# GZ7_1_x-User_Interface.net
KiCad netlist of a schematic drawn in Altium Designer
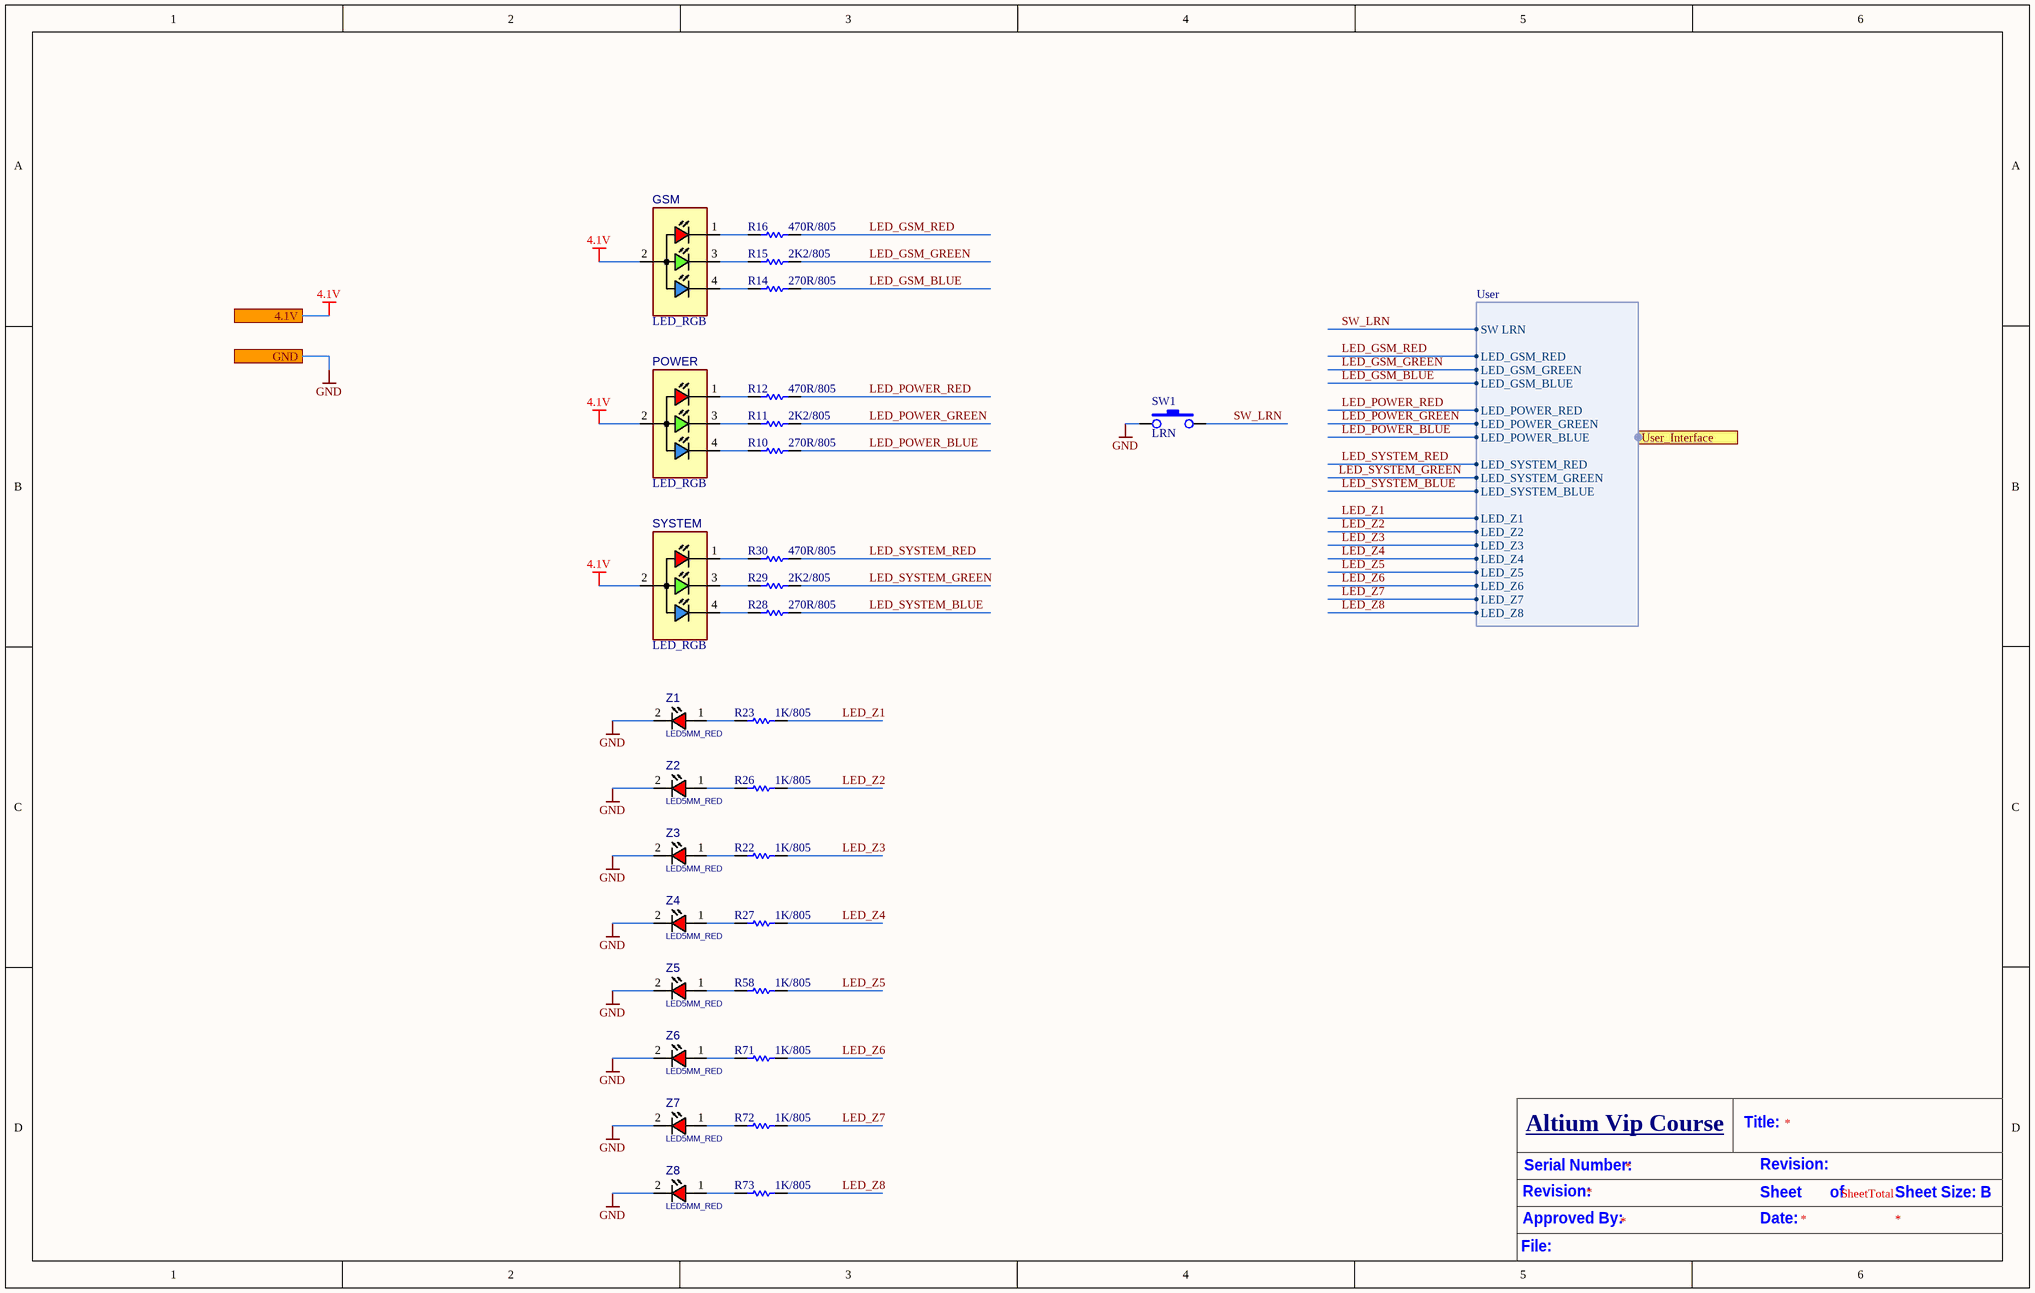
[diagram p0: GZ7_1_x-User_Interface.SchDoc]

(export (version "E")
  (design (tool "Eeschema 10.0.6"))
  (components
    (comp (ref "GSM")
      (value "LED_RGB")
      (footprint "LED5RGB")
      (description "LED, THD, 5MM, RGB COMMON CATHODE")
      (fields (field (name "MANF_P#") "YSL-R596CR3G4B5C-C10") (field (name "MANF") "CHINA YOUNG"))
      (libsource (lib "led(diode)") (part "LED_THD_5MM_RGB_CA"))
    )
    (comp (ref "POWER")
      (value "LED_RGB")
      (footprint "LED5RGB")
      (description "LED, THD, 5MM, RGB COMMON CATHODE")
      (fields (field (name "MANF_P#") "YSL-R596CR3G4B5C-C10") (field (name "MANF") "CHINA YOUNG"))
      (libsource (lib "led(diode)") (part "LED_THD_5MM_RGB_CA"))
    )
    (comp (ref "R10")
      (value "270R/805")
      (footprint "my805")
      (description "RES 805")
      (fields (field (name "DESIGNER") "Abbas Basereh"))
      (libsource (lib "Altium") (part "RES 1206 0.25W"))
    )
    (comp (ref "R11")
      (value "2K2/805")
      (footprint "my805")
      (description "RES 805")
      (fields (field (name "DESIGNER") "Abbas Basereh"))
      (libsource (lib "Altium") (part "RES 1206 0.25W"))
    )
    (comp (ref "R12")
      (value "470R/805")
      (footprint "my805")
      (description "RES 805")
      (fields (field (name "DESIGNER") "Abbas Basereh"))
      (libsource (lib "Altium") (part "RES 1206 0.25W"))
    )
    (comp (ref "R14")
      (value "270R/805")
      (footprint "my805")
      (description "RES 805")
      (fields (field (name "DESIGNER") "Abbas Basereh"))
      (libsource (lib "Altium") (part "RES 1206 0.25W"))
    )
    (comp (ref "R15")
      (value "2K2/805")
      (footprint "my805")
      (description "RES 805")
      (fields (field (name "DESIGNER") "Abbas Basereh"))
      (libsource (lib "Altium") (part "RES 1206 0.25W"))
    )
    (comp (ref "R16")
      (value "470R/805")
      (footprint "my805")
      (description "RES 805")
      (fields (field (name "DESIGNER") "Abbas Basereh"))
      (libsource (lib "Altium") (part "RES 1206 0.25W"))
    )
    (comp (ref "R22")
      (value "1K/805")
      (footprint "my805")
      (description "RES 805")
      (fields (field (name "DESIGNER") "Abbas Basereh"))
      (libsource (lib "Altium") (part "RES 1206 0.25W"))
    )
    (comp (ref "R23")
      (value "1K/805")
      (footprint "my805")
      (description "RES 805")
      (fields (field (name "DESIGNER") "Abbas Basereh"))
      (libsource (lib "Altium") (part "RES 1206 0.25W"))
    )
    (comp (ref "R26")
      (value "1K/805")
      (footprint "my805")
      (description "RES 805")
      (fields (field (name "DESIGNER") "Abbas Basereh"))
      (libsource (lib "Altium") (part "RES 1206 0.25W"))
    )
    (comp (ref "R27")
      (value "1K/805")
      (footprint "my805")
      (description "RES 805")
      (fields (field (name "DESIGNER") "Abbas Basereh"))
      (libsource (lib "Altium") (part "RES 1206 0.25W"))
    )
    (comp (ref "R28")
      (value "270R/805")
      (footprint "my805")
      (description "RES 805")
      (fields (field (name "DESIGNER") "Abbas Basereh"))
      (libsource (lib "Altium") (part "RES 1206 0.25W"))
    )
    (comp (ref "R29")
      (value "2K2/805")
      (footprint "my805")
      (description "RES 805")
      (fields (field (name "DESIGNER") "Abbas Basereh"))
      (libsource (lib "Altium") (part "RES 1206 0.25W"))
    )
    (comp (ref "R30")
      (value "470R/805")
      (footprint "my805")
      (description "RES 805")
      (fields (field (name "DESIGNER") "Abbas Basereh"))
      (libsource (lib "Altium") (part "RES 1206 0.25W"))
    )
    (comp (ref "R58")
      (value "1K/805")
      (footprint "my805")
      (description "RES 805")
      (fields (field (name "DESIGNER") "Abbas Basereh"))
      (libsource (lib "Altium") (part "RES 1206 0.25W"))
    )
    (comp (ref "R71")
      (value "1K/805")
      (footprint "my805")
      (description "RES 805")
      (fields (field (name "DESIGNER") "Abbas Basereh"))
      (libsource (lib "Altium") (part "RES 1206 0.25W"))
    )
    (comp (ref "R72")
      (value "1K/805")
      (footprint "my805")
      (description "RES 805")
      (fields (field (name "DESIGNER") "Abbas Basereh"))
      (libsource (lib "Altium") (part "RES 1206 0.25W"))
    )
    (comp (ref "R73")
      (value "1K/805")
      (footprint "my805")
      (description "RES 805")
      (fields (field (name "DESIGNER") "Abbas Basereh"))
      (libsource (lib "Altium") (part "RES 1206 0.25W"))
    )
    (comp (ref "SW1")
      (value "LRN")
      (footprint "SWPBS_SPST_6X3X5")
      (libsource (lib "AliPadash") (part "SW-PB"))
    )
    (comp (ref "SYSTEM")
      (value "LED_RGB")
      (footprint "LED5RGB")
      (description "LED, THD, 5MM, RGB COMMON CATHODE")
      (fields (field (name "MANF_P#") "YSL-R596CR3G4B5C-C10") (field (name "MANF") "CHINA YOUNG"))
      (libsource (lib "led(diode)") (part "LED_THD_5MM_RGB_CA"))
    )
    (comp (ref "Z1")
      (value "LED5MM_RED")
      (footprint "LED_SMD_0805")
      (description "LED, THD, 5MM, RED")
      (fields (field (name "MANF") "MANF") (field (name "MANF_P#") "MANF_PART#"))
      (libsource (lib "led(diode)") (part "LED_THD_5MM_RED"))
    )
    (comp (ref "Z2")
      (value "LED5MM_RED")
      (footprint "LED_SMD_0805")
      (description "LED, THD, 5MM, RED")
      (fields (field (name "MANF") "MANF") (field (name "MANF_P#") "MANF_PART#"))
      (libsource (lib "led(diode)") (part "LED_THD_5MM_RED"))
    )
    (comp (ref "Z3")
      (value "LED5MM_RED")
      (footprint "LED_SMD_0805")
      (description "LED, THD, 5MM, RED")
      (fields (field (name "MANF") "MANF") (field (name "MANF_P#") "MANF_PART#"))
      (libsource (lib "led(diode)") (part "LED_THD_5MM_RED"))
    )
    (comp (ref "Z4")
      (value "LED5MM_RED")
      (footprint "LED_SMD_0805")
      (description "LED, THD, 5MM, RED")
      (fields (field (name "MANF") "MANF") (field (name "MANF_P#") "MANF_PART#"))
      (libsource (lib "led(diode)") (part "LED_THD_5MM_RED"))
    )
    (comp (ref "Z5")
      (value "LED5MM_RED")
      (footprint "LED_SMD_0805")
      (description "LED, THD, 5MM, RED")
      (fields (field (name "MANF") "MANF") (field (name "MANF_P#") "MANF_PART#"))
      (libsource (lib "led(diode)") (part "LED_THD_5MM_RED"))
    )
    (comp (ref "Z6")
      (value "LED5MM_RED")
      (footprint "LED_SMD_0805")
      (description "LED, THD, 5MM, RED")
      (fields (field (name "MANF") "MANF") (field (name "MANF_P#") "MANF_PART#"))
      (libsource (lib "led(diode)") (part "LED_THD_5MM_RED"))
    )
    (comp (ref "Z7")
      (value "LED5MM_RED")
      (footprint "LED_SMD_0805")
      (description "LED, THD, 5MM, RED")
      (fields (field (name "MANF") "MANF") (field (name "MANF_P#") "MANF_PART#"))
      (libsource (lib "led(diode)") (part "LED_THD_5MM_RED"))
    )
    (comp (ref "Z8")
      (value "LED5MM_RED")
      (footprint "LED_SMD_0805")
      (description "LED, THD, 5MM, RED")
      (fields (field (name "MANF") "MANF") (field (name "MANF_P#") "MANF_PART#"))
      (libsource (lib "led(diode)") (part "LED_THD_5MM_RED"))
    )
  )
  (nets
    (net (code "2") (name "/LED_GSM_BLUE") (class "Default")
      (node (ref "R14") (pin "2") (pinfunction "2_2") (pintype "passive"))
    )
    (net (code "3") (name "/LED_GSM_GREEN") (class "Default")
      (node (ref "R15") (pin "2") (pinfunction "2_2") (pintype "passive"))
    )
    (net (code "4") (name "/LED_GSM_RED") (class "Default")
      (node (ref "R16") (pin "2") (pinfunction "2_2") (pintype "passive"))
    )
    (net (code "5") (name "/LED_POWER_BLUE") (class "Default")
      (node (ref "R10") (pin "2") (pinfunction "2_2") (pintype "passive"))
    )
    (net (code "6") (name "/LED_POWER_GREEN") (class "Default")
      (node (ref "R11") (pin "2") (pinfunction "2_2") (pintype "passive"))
    )
    (net (code "7") (name "/LED_POWER_RED") (class "Default")
      (node (ref "R12") (pin "2") (pinfunction "2_2") (pintype "passive"))
    )
    (net (code "8") (name "/LED_SYSTEM_BLUE") (class "Default")
      (node (ref "R28") (pin "2") (pinfunction "2_2") (pintype "passive"))
    )
    (net (code "9") (name "/LED_SYSTEM_GREEN") (class "Default")
      (node (ref "R29") (pin "2") (pinfunction "2_2") (pintype "passive"))
    )
    (net (code "10") (name "/LED_SYSTEM_RED") (class "Default")
      (node (ref "R30") (pin "2") (pinfunction "2_2") (pintype "passive"))
    )
    (net (code "11") (name "/LED_Z1") (class "Default")
      (node (ref "R23") (pin "2") (pinfunction "2_2") (pintype "passive"))
    )
    (net (code "12") (name "/LED_Z2") (class "Default")
      (node (ref "R26") (pin "2") (pinfunction "2_2") (pintype "passive"))
    )
    (net (code "13") (name "/LED_Z3") (class "Default")
      (node (ref "R22") (pin "2") (pinfunction "2_2") (pintype "passive"))
    )
    (net (code "14") (name "/LED_Z4") (class "Default")
      (node (ref "R27") (pin "2") (pinfunction "2_2") (pintype "passive"))
    )
    (net (code "15") (name "/LED_Z5") (class "Default")
      (node (ref "R58") (pin "2") (pinfunction "2_2") (pintype "passive"))
    )
    (net (code "16") (name "/LED_Z6") (class "Default")
      (node (ref "R71") (pin "2") (pinfunction "2_2") (pintype "passive"))
    )
    (net (code "17") (name "/LED_Z7") (class "Default")
      (node (ref "R72") (pin "2") (pinfunction "2_2") (pintype "passive"))
    )
    (net (code "18") (name "/LED_Z8") (class "Default")
      (node (ref "R73") (pin "2") (pinfunction "2_2") (pintype "passive"))
    )
    (net (code "19") (name "/SW_LRN") (class "Default") (node (ref "SW1") (pin "2") (pintype "passive")))
    (net (code "21") (name "4.1V") (class "Default")
      (node (ref "GSM") (pin "2") (pinfunction "C_2") (pintype "passive"))
      (node (ref "POWER") (pin "2") (pinfunction "C_2") (pintype "passive"))
      (node (ref "SYSTEM") (pin "2") (pinfunction "C_2") (pintype "passive"))
    )
    (net (code "22") (name "GND") (class "Default")
      (node (ref "SW1") (pin "1") (pintype "passive"))
      (node (ref "Z1") (pin "2") (pinfunction "CATHODE_2") (pintype "passive"))
      (node (ref "Z2") (pin "2") (pinfunction "CATHODE_2") (pintype "passive"))
      (node (ref "Z3") (pin "2") (pinfunction "CATHODE_2") (pintype "passive"))
      (node (ref "Z4") (pin "2") (pinfunction "CATHODE_2") (pintype "passive"))
      (node (ref "Z5") (pin "2") (pinfunction "CATHODE_2") (pintype "passive"))
      (node (ref "Z6") (pin "2") (pinfunction "CATHODE_2") (pintype "passive"))
      (node (ref "Z7") (pin "2") (pinfunction "CATHODE_2") (pintype "passive"))
      (node (ref "Z8") (pin "2") (pinfunction "CATHODE_2") (pintype "passive"))
    )
    (net (code "23") (name "Net-(GSM-BLU)") (class "Default")
      (node (ref "GSM") (pin "4") (pinfunction "BLU_4") (pintype "passive"))
      (node (ref "R14") (pin "1") (pinfunction "1_1") (pintype "passive"))
    )
    (net (code "24") (name "Net-(GSM-GRN)") (class "Default")
      (node (ref "GSM") (pin "3") (pinfunction "GRN_3") (pintype "passive"))
      (node (ref "R15") (pin "1") (pinfunction "1_1") (pintype "passive"))
    )
    (net (code "25") (name "Net-(GSM-RED)") (class "Default")
      (node (ref "GSM") (pin "1") (pinfunction "RED_1") (pintype "passive"))
      (node (ref "R16") (pin "1") (pinfunction "1_1") (pintype "passive"))
    )
    (net (code "26") (name "Net-(POWER-BLU)") (class "Default")
      (node (ref "POWER") (pin "4") (pinfunction "BLU_4") (pintype "passive"))
      (node (ref "R10") (pin "1") (pinfunction "1_1") (pintype "passive"))
    )
    (net (code "27") (name "Net-(POWER-GRN)") (class "Default")
      (node (ref "POWER") (pin "3") (pinfunction "GRN_3") (pintype "passive"))
      (node (ref "R11") (pin "1") (pinfunction "1_1") (pintype "passive"))
    )
    (net (code "28") (name "Net-(POWER-RED)") (class "Default")
      (node (ref "POWER") (pin "1") (pinfunction "RED_1") (pintype "passive"))
      (node (ref "R12") (pin "1") (pinfunction "1_1") (pintype "passive"))
    )
    (net (code "29") (name "Net-(SYSTEM-BLU)") (class "Default")
      (node (ref "R28") (pin "1") (pinfunction "1_1") (pintype "passive"))
      (node (ref "SYSTEM") (pin "4") (pinfunction "BLU_4") (pintype "passive"))
    )
    (net (code "30") (name "Net-(SYSTEM-GRN)") (class "Default")
      (node (ref "R29") (pin "1") (pinfunction "1_1") (pintype "passive"))
      (node (ref "SYSTEM") (pin "3") (pinfunction "GRN_3") (pintype "passive"))
    )
    (net (code "31") (name "Net-(SYSTEM-RED)") (class "Default")
      (node (ref "R30") (pin "1") (pinfunction "1_1") (pintype "passive"))
      (node (ref "SYSTEM") (pin "1") (pinfunction "RED_1") (pintype "passive"))
    )
    (net (code "32") (name "Net-(Z1-ANODE)") (class "Default")
      (node (ref "R23") (pin "1") (pinfunction "1_1") (pintype "passive"))
      (node (ref "Z1") (pin "1") (pinfunction "ANODE_1") (pintype "passive"))
    )
    (net (code "33") (name "Net-(Z2-ANODE)") (class "Default")
      (node (ref "R26") (pin "1") (pinfunction "1_1") (pintype "passive"))
      (node (ref "Z2") (pin "1") (pinfunction "ANODE_1") (pintype "passive"))
    )
    (net (code "34") (name "Net-(Z3-ANODE)") (class "Default")
      (node (ref "R22") (pin "1") (pinfunction "1_1") (pintype "passive"))
      (node (ref "Z3") (pin "1") (pinfunction "ANODE_1") (pintype "passive"))
    )
    (net (code "35") (name "Net-(Z4-ANODE)") (class "Default")
      (node (ref "R27") (pin "1") (pinfunction "1_1") (pintype "passive"))
      (node (ref "Z4") (pin "1") (pinfunction "ANODE_1") (pintype "passive"))
    )
    (net (code "36") (name "Net-(Z5-ANODE)") (class "Default")
      (node (ref "R58") (pin "1") (pinfunction "1_1") (pintype "passive"))
      (node (ref "Z5") (pin "1") (pinfunction "ANODE_1") (pintype "passive"))
    )
    (net (code "37") (name "Net-(Z6-ANODE)") (class "Default")
      (node (ref "R71") (pin "1") (pinfunction "1_1") (pintype "passive"))
      (node (ref "Z6") (pin "1") (pinfunction "ANODE_1") (pintype "passive"))
    )
    (net (code "38") (name "Net-(Z7-ANODE)") (class "Default")
      (node (ref "R72") (pin "1") (pinfunction "1_1") (pintype "passive"))
      (node (ref "Z7") (pin "1") (pinfunction "ANODE_1") (pintype "passive"))
    )
    (net (code "39") (name "Net-(Z8-ANODE)") (class "Default")
      (node (ref "R73") (pin "1") (pinfunction "1_1") (pintype "passive"))
      (node (ref "Z8") (pin "1") (pinfunction "ANODE_1") (pintype "passive"))
    )
  )
)
